# FanController_ATtiny4313.net
KiCad netlist of a schematic drawn in EAGLE
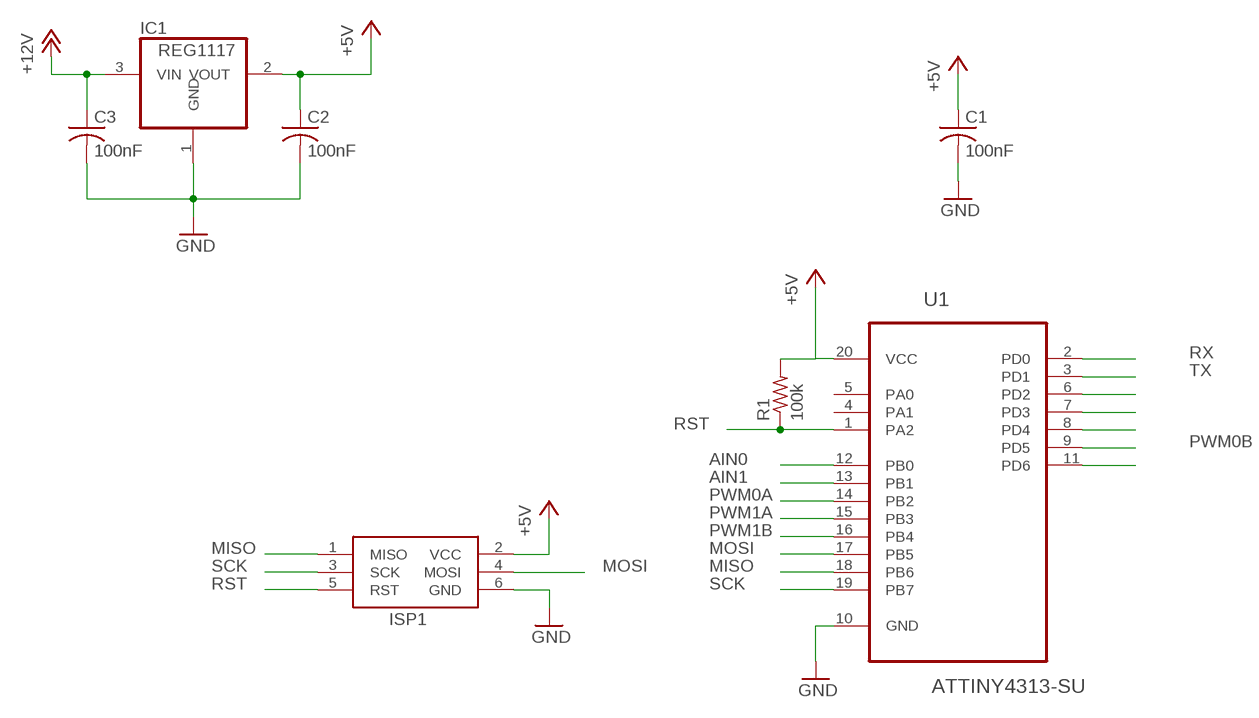
[diagram p0: schematic, sheet 1]

(export (version "E")
  (design (tool "Eeschema 10.0.6"))
  (components
    (comp (ref "C1")
      (value "100nF")
      (footprint "eagle-import:C0805")
      (libsource (lib "eagle-import") (part "C-USC0805"))
    )
    (comp (ref "C2")
      (value "100nF")
      (footprint "eagle-import:C0805")
      (libsource (lib "eagle-import") (part "C-USC0805"))
    )
    (comp (ref "C3")
      (value "100nF")
      (footprint "eagle-import:C0805")
      (libsource (lib "eagle-import") (part "C-USC0805"))
    )
    (comp (ref "IC1")
      (value "REG1117")
      (footprint "eagle-import:SOT223")
      (libsource (lib "eagle-import") (part "REG1117"))
    )
    (comp (ref "ISP1")
      (value "AVRISP-6")
      (footprint "eagle-import:AVRISP")
      (libsource (lib "eagle-import") (part "AVRISP-6"))
    )
    (comp (ref "R1")
      (value "100k")
      (footprint "eagle-import:R0805")
      (libsource (lib "eagle-import") (part "R-US_R0805"))
    )
    (comp (ref "U1")
      (value "ATTINY4313-SU")
      (footprint "eagle-import:SOIC127P1032X265-20N")
      (libsource (lib "eagle-import") (part "ATTINY4313-SU"))
    )
  )
  (nets
    (net (code "1") (name "+5V") (class "Default")
      (node (ref "C1") (pin "1") (pinfunction "1_1") (pintype "passive"))
      (node (ref "C2") (pin "1") (pinfunction "1_1") (pintype "passive"))
      (node (ref "IC1") (pin "2") (pinfunction "VOUT_2") (pintype "output"))
      (node (ref "ISP1") (pin "2") (pinfunction "VCC_2") (pintype "power_in"))
      (node (ref "R1") (pin "2") (pinfunction "2_2") (pintype "passive"))
      (node (ref "U1") (pin "20") (pinfunction "VCC_20") (pintype "power_in"))
    )
    (net (code "2") (name "+12V") (class "Default")
      (node (ref "C3") (pin "1") (pinfunction "1_1") (pintype "passive"))
      (node (ref "IC1") (pin "3") (pinfunction "VIN_3") (pintype "input"))
    )
    (net (code "3") (name "/AIN0") (class "Default")
      (node (ref "U1") (pin "12") (pinfunction "PB0_12") (pintype "bidirectional"))
    )
    (net (code "4") (name "/AIN1") (class "Default")
      (node (ref "U1") (pin "13") (pinfunction "PB1_13") (pintype "bidirectional"))
    )
    (net (code "5") (name "/MISO") (class "Default")
      (node (ref "ISP1") (pin "1") (pinfunction "MISO_1") (pintype "input"))
      (node (ref "U1") (pin "18") (pinfunction "PB6_18") (pintype "bidirectional"))
    )
    (net (code "6") (name "/MOSI") (class "Default")
      (node (ref "ISP1") (pin "4") (pinfunction "MOSI_4") (pintype "output"))
      (node (ref "U1") (pin "17") (pinfunction "PB5_17") (pintype "bidirectional"))
    )
    (net (code "7") (name "/PWM0A") (class "Default")
      (node (ref "U1") (pin "14") (pinfunction "PB2_14") (pintype "bidirectional"))
    )
    (net (code "8") (name "/PWM0B") (class "Default")
      (node (ref "U1") (pin "9") (pinfunction "PD5_9") (pintype "bidirectional"))
    )
    (net (code "9") (name "/PWM1A") (class "Default")
      (node (ref "U1") (pin "15") (pinfunction "PB3_15") (pintype "bidirectional"))
    )
    (net (code "10") (name "/PWM1B") (class "Default")
      (node (ref "U1") (pin "16") (pinfunction "PB4_16") (pintype "bidirectional"))
    )
    (net (code "11") (name "/RST") (class "Default")
      (node (ref "ISP1") (pin "5") (pinfunction "RST_5") (pintype "output"))
      (node (ref "R1") (pin "1") (pinfunction "1_1") (pintype "passive"))
      (node (ref "U1") (pin "1") (pinfunction "PA2_1") (pintype "bidirectional"))
    )
    (net (code "12") (name "/RX") (class "Default")
      (node (ref "U1") (pin "2") (pinfunction "PD0_2") (pintype "bidirectional"))
    )
    (net (code "13") (name "/SCK") (class "Default")
      (node (ref "ISP1") (pin "3") (pinfunction "SCK_3") (pintype "output"))
      (node (ref "U1") (pin "19") (pinfunction "PB7_19") (pintype "bidirectional"))
    )
    (net (code "14") (name "/TX") (class "Default")
      (node (ref "U1") (pin "3") (pinfunction "PD1_3") (pintype "bidirectional"))
    )
    (net (code "15") (name "GND") (class "Default")
      (node (ref "C1") (pin "2") (pinfunction "2_2") (pintype "passive"))
      (node (ref "C2") (pin "2") (pinfunction "2_2") (pintype "passive"))
      (node (ref "C3") (pin "2") (pinfunction "2_2") (pintype "passive"))
      (node (ref "IC1") (pin "1") (pinfunction "GND_1") (pintype "power_in"))
      (node (ref "ISP1") (pin "6") (pinfunction "GND_6") (pintype "power_in"))
      (node (ref "U1") (pin "10") (pinfunction "GND_10") (pintype "passive"))
    )
    (net (code "16") (name "unconnected-(U1-PA0-Pad5)") (class "Default")
      (node (ref "U1") (pin "5") (pinfunction "PA0_5") (pintype "bidirectional"))
    )
    (net (code "17") (name "unconnected-(U1-PA1-Pad4)") (class "Default")
      (node (ref "U1") (pin "4") (pinfunction "PA1_4") (pintype "bidirectional"))
    )
    (net (code "18") (name "unconnected-(U1-PD2-Pad6)") (class "Default")
      (node (ref "U1") (pin "6") (pinfunction "PD2_6") (pintype "bidirectional"))
    )
    (net (code "19") (name "unconnected-(U1-PD3-Pad7)") (class "Default")
      (node (ref "U1") (pin "7") (pinfunction "PD3_7") (pintype "bidirectional"))
    )
    (net (code "20") (name "unconnected-(U1-PD4-Pad8)") (class "Default")
      (node (ref "U1") (pin "8") (pinfunction "PD4_8") (pintype "bidirectional"))
    )
    (net (code "21") (name "unconnected-(U1-PD6-Pad11)") (class "Default")
      (node (ref "U1") (pin "11") (pinfunction "PD6_11") (pintype "bidirectional"))
    )
  )
)
